# PCB_Minisumo_2018_Educatiu.net
KiCad netlist of a schematic drawn in EAGLE
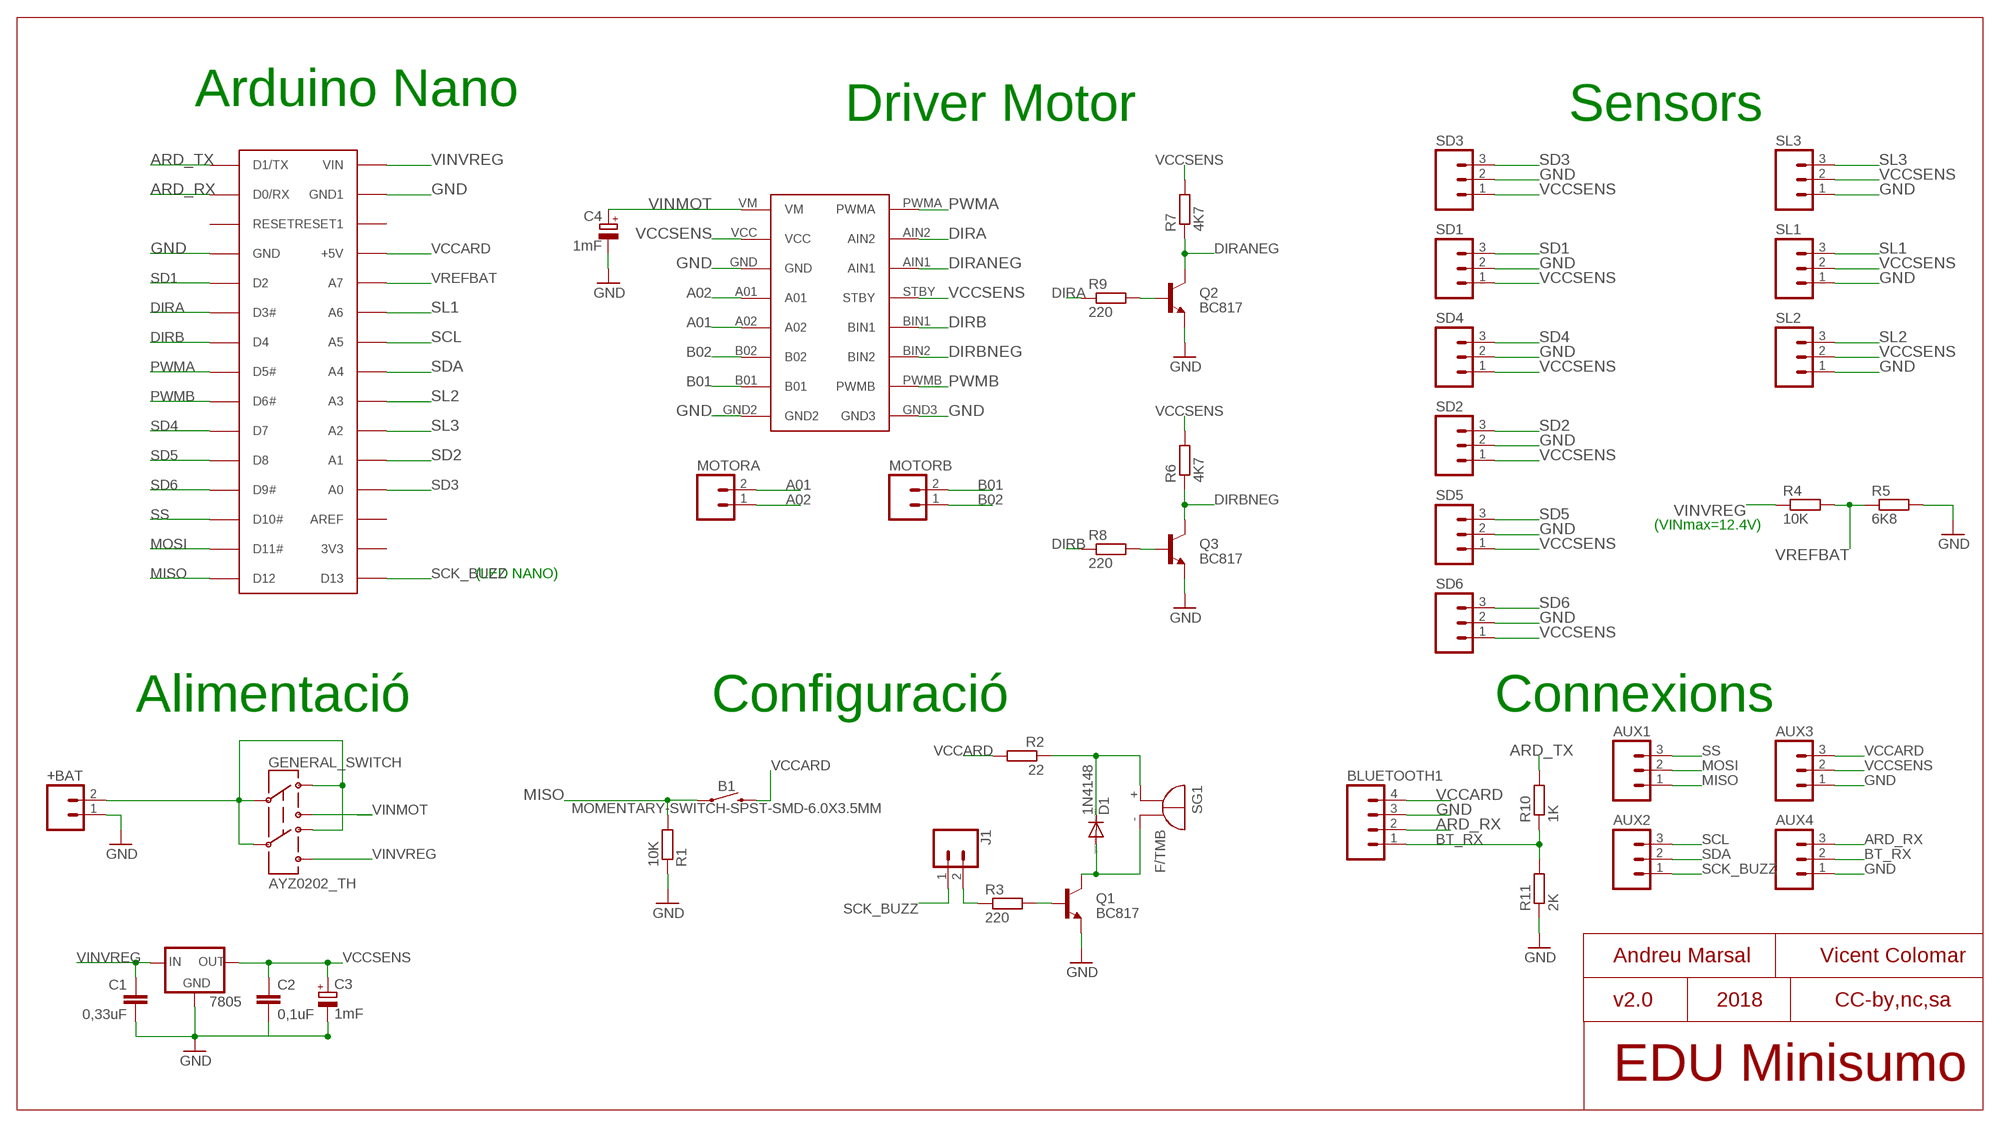
[diagram p0: schematic, sheet 1]
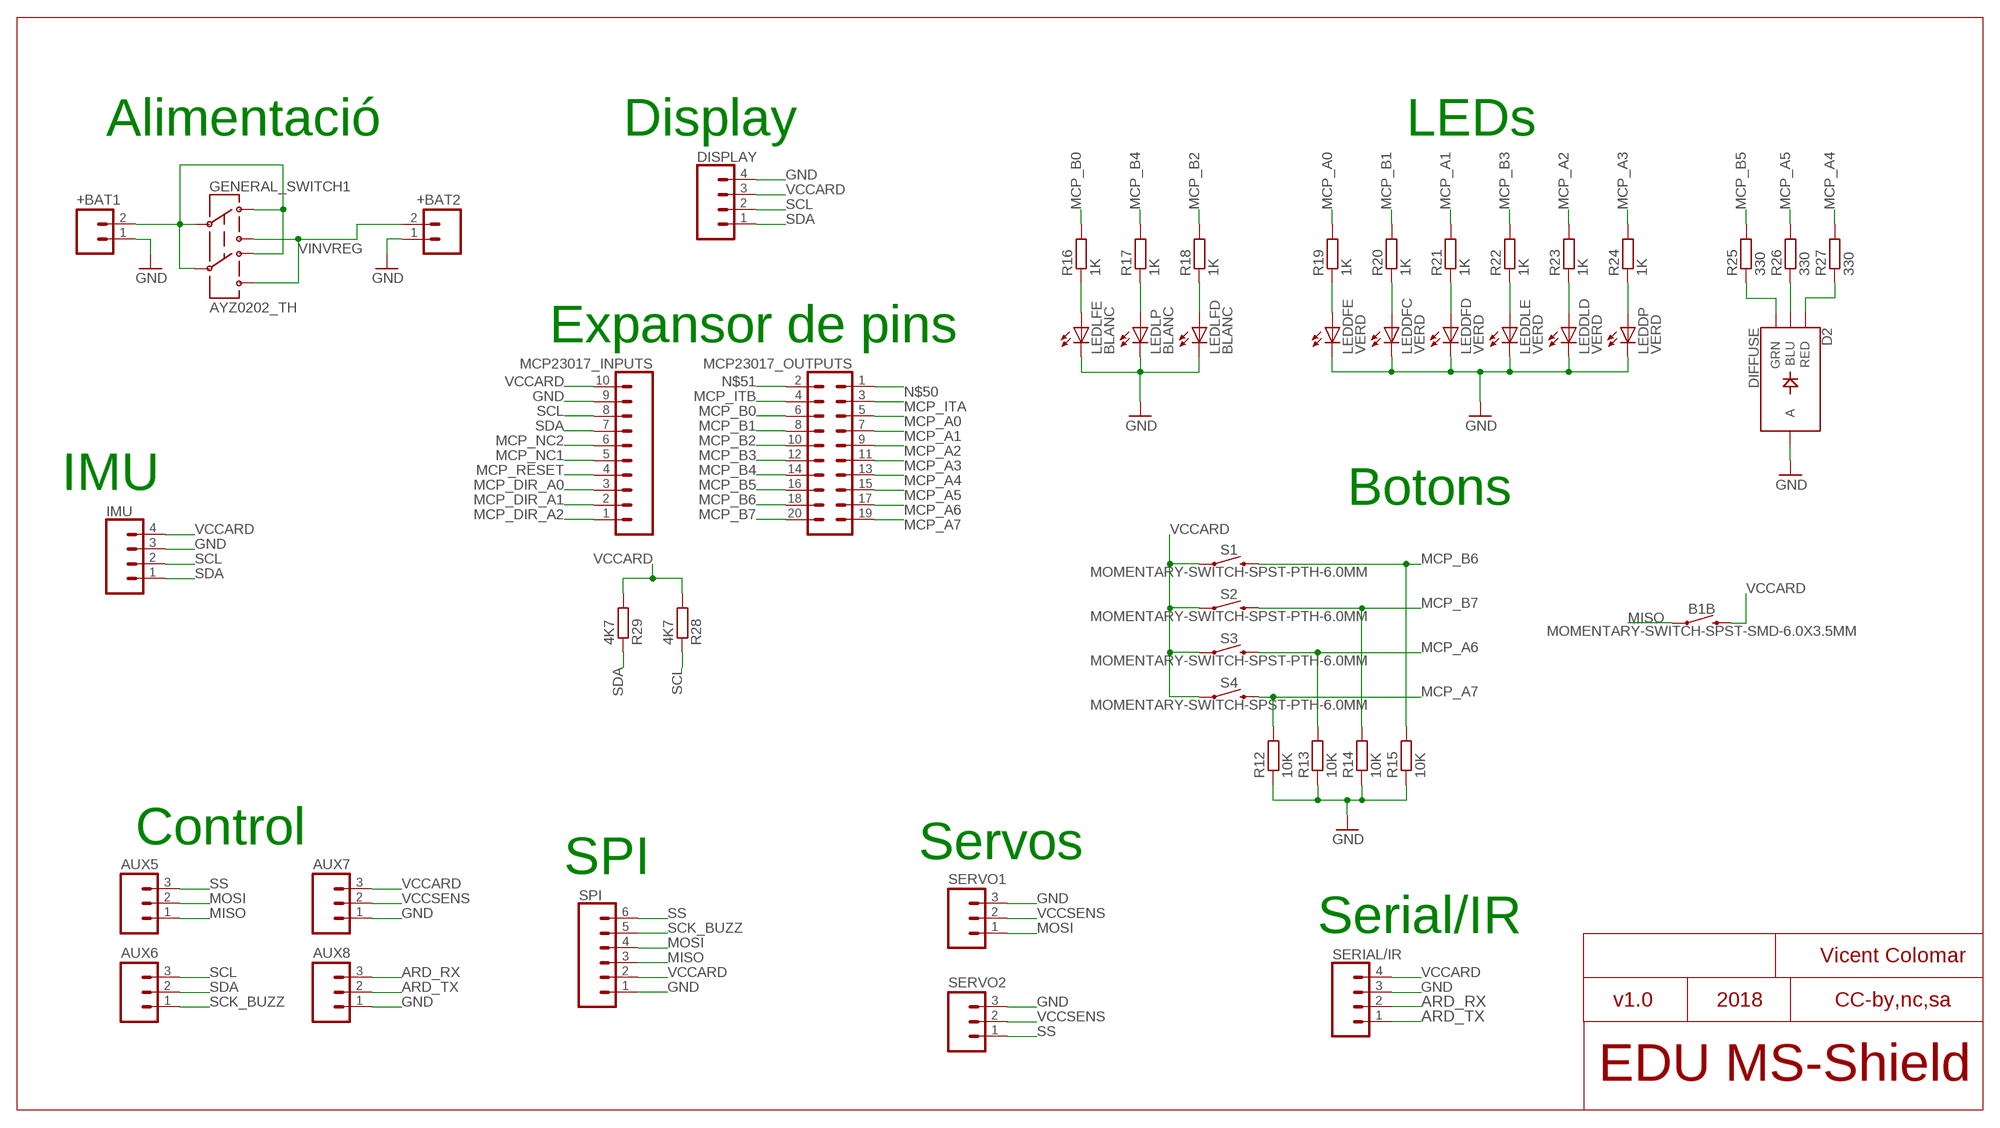
[diagram p1: schematic, sheet 2]

(export (version "E")
  (design (tool "Eeschema 10.0.6"))
  (components
    (comp (ref "+BAT")
      (value "M02LOCK_LONGPADS")
      (footprint "eagle-import:1X02_LOCK_LONGPADS")
      (libsource (lib "eagle-import") (part "M02LOCK_LONGPADS"))
    )
    (comp (ref "7805")
      (value "V_REG_78XXSINK")
      (footprint "eagle-import:TO220-IGO")
      (libsource (lib "eagle-import") (part "V_REG_78XXSINK"))
    )
    (comp (ref "AUX1")
      (value "M03PTH")
      (footprint "eagle-import:1X03")
      (libsource (lib "eagle-import") (part "M03PTH"))
    )
    (comp (ref "AUX2")
      (value "M03PTH")
      (footprint "eagle-import:1X03")
      (libsource (lib "eagle-import") (part "M03PTH"))
    )
    (comp (ref "AUX3")
      (value "M03PTH")
      (footprint "eagle-import:1X03")
      (libsource (lib "eagle-import") (part "M03PTH"))
    )
    (comp (ref "AUX4")
      (value "M03PTH")
      (footprint "eagle-import:1X03")
      (libsource (lib "eagle-import") (part "M03PTH"))
    )
    (comp (ref "B1")
      (value "MOMENTARY-SWITCH-SPST-SMD-6.0X3.5MM")
      (footprint "eagle-import:TACTILE_SWITCH_SMD_6.0X3.5MM")
      (libsource (lib "eagle-import") (part "MOMENTARY-SWITCH-SPST-SMD-6.0X3.5MM"))
    )
    (comp (ref "BLUETOOTH1")
      (value "M04PTH")
      (footprint "eagle-import:1X04")
      (libsource (lib "eagle-import") (part "M04PTH"))
    )
    (comp (ref "C1")
      (value "0,33uF")
      (footprint "eagle-import:C1206K")
      (libsource (lib "eagle-import") (part "C-EUC1206K"))
    )
    (comp (ref "C2")
      (value "0,1uF")
      (footprint "eagle-import:C1206K")
      (libsource (lib "eagle-import") (part "C-EUC1206K"))
    )
    (comp (ref "C3")
      (value "1mF")
      (footprint "eagle-import:E2,5-6")
      (libsource (lib "eagle-import") (part "CPOL-EUE2.5-6"))
    )
    (comp (ref "C4")
      (value "1mF")
      (footprint "eagle-import:E2,5-6")
      (libsource (lib "eagle-import") (part "CPOL-EUE2.5-6"))
    )
    (comp (ref "D1")
      (value "1N4148")
      (footprint "eagle-import:SOD106-R")
      (libsource (lib "eagle-import") (part "DIODE-SOD106-R"))
    )
    (comp (ref "GENERAL_SWITCH")
      (value "AYZ0202_TH")
      (footprint "eagle-import:AYZ0202_TH")
      (libsource (lib "eagle-import") (part "AYZ0202_TH"))
    )
    (comp (ref "J1")
      (value "CONN_02")
      (footprint "eagle-import:1X02")
      (libsource (lib "eagle-import") (part "CONN_02"))
    )
    (comp (ref "MOTORA")
      (value "M023.5MM")
      (footprint "eagle-import:SCREWTERMINAL-3.5MM-2")
      (libsource (lib "eagle-import") (part "M023.5MM"))
    )
    (comp (ref "MOTORB")
      (value "M023.5MM")
      (footprint "eagle-import:SCREWTERMINAL-3.5MM-2")
      (libsource (lib "eagle-import") (part "M023.5MM"))
    )
    (comp (ref "Q1")
      (value "BC817")
      (footprint "eagle-import:TO-92")
      (libsource (lib "eagle-import") (part "TRANSISTOR_NPNTO92"))
    )
    (comp (ref "Q2")
      (value "BC817")
      (footprint "eagle-import:TO-92")
      (libsource (lib "eagle-import") (part "TRANSISTOR_NPNTO92"))
    )
    (comp (ref "Q3")
      (value "BC817")
      (footprint "eagle-import:TO-92")
      (libsource (lib "eagle-import") (part "TRANSISTOR_NPNTO92"))
    )
    (comp (ref "R1")
      (value "10K")
      (footprint "eagle-import:R1206")
      (libsource (lib "eagle-import") (part "resistor_348_R-EU_R1206"))
    )
    (comp (ref "R2")
      (value "22")
      (footprint "eagle-import:R1206")
      (libsource (lib "eagle-import") (part "resistor_348_R-EU_R1206"))
    )
    (comp (ref "R3")
      (value "220")
      (footprint "eagle-import:M1206")
      (libsource (lib "eagle-import") (part "R-EU_M1206"))
    )
    (comp (ref "R4")
      (value "10K")
      (footprint "eagle-import:R1206")
      (libsource (lib "eagle-import") (part "resistor_348_R-EU_R1206"))
    )
    (comp (ref "R5")
      (value "6K8")
      (footprint "eagle-import:R1206")
      (libsource (lib "eagle-import") (part "resistor_348_R-EU_R1206"))
    )
    (comp (ref "R6")
      (value "4K7")
      (footprint "eagle-import:M1206")
      (libsource (lib "eagle-import") (part "R-EU_M1206"))
    )
    (comp (ref "R7")
      (value "4K7")
      (footprint "eagle-import:M1206")
      (libsource (lib "eagle-import") (part "R-EU_M1206"))
    )
    (comp (ref "R8")
      (value "220")
      (footprint "eagle-import:M1206")
      (libsource (lib "eagle-import") (part "R-EU_M1206"))
    )
    (comp (ref "R9")
      (value "220")
      (footprint "eagle-import:M1206")
      (libsource (lib "eagle-import") (part "R-EU_M1206"))
    )
    (comp (ref "R10")
      (value "1K")
      (footprint "eagle-import:R1206")
      (libsource (lib "eagle-import") (part "resistor_348_R-EU_R1206"))
    )
    (comp (ref "R11")
      (value "2K")
      (footprint "eagle-import:R1206")
      (libsource (lib "eagle-import") (part "resistor_348_R-EU_R1206"))
    )
    (comp (ref "SD1")
      (value "M03PTH")
      (footprint "eagle-import:1X03")
      (libsource (lib "eagle-import") (part "M03PTH"))
    )
    (comp (ref "SD2")
      (value "M03PTH")
      (footprint "eagle-import:1X03")
      (libsource (lib "eagle-import") (part "M03PTH"))
    )
    (comp (ref "SD3")
      (value "M03PTH")
      (footprint "eagle-import:1X03")
      (libsource (lib "eagle-import") (part "M03PTH"))
    )
    (comp (ref "SD4")
      (value "M03PTH")
      (footprint "eagle-import:1X03")
      (libsource (lib "eagle-import") (part "M03PTH"))
    )
    (comp (ref "SD5")
      (value "M03PTH")
      (footprint "eagle-import:1X03")
      (libsource (lib "eagle-import") (part "M03PTH"))
    )
    (comp (ref "SD6")
      (value "M03PTH")
      (footprint "eagle-import:1X03")
      (libsource (lib "eagle-import") (part "M03PTH"))
    )
    (comp (ref "SG1")
      (value "F/TMB")
      (footprint "eagle-import:F_TMB")
      (libsource (lib "eagle-import") (part "F/TMB"))
    )
    (comp (ref "SL1")
      (value "M03PTH")
      (footprint "eagle-import:1X03")
      (libsource (lib "eagle-import") (part "M03PTH"))
    )
    (comp (ref "SL2")
      (value "M03PTH")
      (footprint "eagle-import:1X03")
      (libsource (lib "eagle-import") (part "M03PTH"))
    )
    (comp (ref "SL3")
      (value "M03PTH")
      (footprint "eagle-import:1X03")
      (libsource (lib "eagle-import") (part "M03PTH"))
    )
    (comp (ref "U$1")
      (value "ARDUINONANONOHOLES")
      (footprint "eagle-import:PDIP-32NOHOLES")
      (libsource (lib "eagle-import") (part "ARDUINONANONOHOLES"))
    )
    (comp (ref "U$2")
      (value "TB6612FNG_SPARKFUN")
      (footprint "eagle-import:TB6612FNG_SPARKFUN")
      (libsource (lib "eagle-import") (part "TB6612FNG_SPARKFUN"))
    )
    (comp (ref "+BAT1")
      (value "M02LOCK_LONGPADS")
      (footprint "eagle-import:1X02_LOCK_LONGPADS")
      (libsource (lib "eagle-import") (part "M02LOCK_LONGPADS"))
    )
    (comp (ref "+BAT2")
      (value "M02LOCK_LONGPADS")
      (footprint "eagle-import:1X02_LOCK_LONGPADS")
      (libsource (lib "eagle-import") (part "M02LOCK_LONGPADS"))
    )
    (comp (ref "AUX5")
      (value "M03PTH")
      (footprint "eagle-import:1X03")
      (libsource (lib "eagle-import") (part "M03PTH"))
    )
    (comp (ref "AUX6")
      (value "M03PTH")
      (footprint "eagle-import:1X03")
      (libsource (lib "eagle-import") (part "M03PTH"))
    )
    (comp (ref "AUX7")
      (value "M03PTH")
      (footprint "eagle-import:1X03")
      (libsource (lib "eagle-import") (part "M03PTH"))
    )
    (comp (ref "AUX8")
      (value "M03PTH")
      (footprint "eagle-import:1X03")
      (libsource (lib "eagle-import") (part "M03PTH"))
    )
    (comp (ref "B1B")
      (value "MOMENTARY-SWITCH-SPST-SMD-6.0X3.5MM")
      (footprint "eagle-import:TACTILE_SWITCH_SMD_6.0X3.5MM")
      (libsource (lib "eagle-import") (part "MOMENTARY-SWITCH-SPST-SMD-6.0X3.5MM"))
    )
    (comp (ref "D2")
      (value "DIFFUSE")
      (footprint "eagle-import:LED-RGB-THRU")
      (libsource (lib "eagle-import") (part "LED-RGB-CADIFFUSE"))
    )
    (comp (ref "DISPLAY")
      (value "CONN_04")
      (footprint "eagle-import:1X04")
      (libsource (lib "eagle-import") (part "CONN_04"))
    )
    (comp (ref "GENERAL_SWITCH1")
      (value "AYZ0202_TH")
      (footprint "eagle-import:AYZ0202_TH")
      (libsource (lib "eagle-import") (part "AYZ0202_TH"))
    )
    (comp (ref "IMU")
      (value "CONN_04")
      (footprint "eagle-import:1X04")
      (libsource (lib "eagle-import") (part "CONN_04"))
    )
    (comp (ref "LEDDFC")
      (value "VERD")
      (footprint "eagle-import:1206")
      (libsource (lib "eagle-import") (part "LEDSMT1206"))
    )
    (comp (ref "LEDDFD")
      (value "VERD")
      (footprint "eagle-import:1206")
      (libsource (lib "eagle-import") (part "LEDSMT1206"))
    )
    (comp (ref "LEDDFE")
      (value "VERD")
      (footprint "eagle-import:1206")
      (libsource (lib "eagle-import") (part "LEDSMT1206"))
    )
    (comp (ref "LEDDLD")
      (value "VERD")
      (footprint "eagle-import:1206")
      (libsource (lib "eagle-import") (part "LEDSMT1206"))
    )
    (comp (ref "LEDDLE")
      (value "VERD")
      (footprint "eagle-import:1206")
      (libsource (lib "eagle-import") (part "LEDSMT1206"))
    )
    (comp (ref "LEDDP")
      (value "VERD")
      (footprint "eagle-import:1206")
      (libsource (lib "eagle-import") (part "LEDSMT1206"))
    )
    (comp (ref "LEDLFD")
      (value "BLANC")
      (footprint "eagle-import:1206")
      (libsource (lib "eagle-import") (part "LEDSMT1206"))
    )
    (comp (ref "LEDLFE")
      (value "BLANC")
      (footprint "eagle-import:1206")
      (libsource (lib "eagle-import") (part "LEDSMT1206"))
    )
    (comp (ref "LEDLP")
      (value "BLANC")
      (footprint "eagle-import:1206")
      (libsource (lib "eagle-import") (part "LEDSMT1206"))
    )
    (comp (ref "MCP23017_INPUTS")
      (value "CONN_10\"")
      (footprint "eagle-import:1X10")
      (libsource (lib "eagle-import") (part "CONN_10{dblquote}"))
    )
    (comp (ref "MCP23017_OUTPUTS")
      (value "CONN_10X2")
      (footprint "eagle-import:2X10")
      (libsource (lib "eagle-import") (part "CONN_10X2"))
    )
    (comp (ref "R12")
      (value "10K")
      (footprint "eagle-import:M1206")
      (libsource (lib "eagle-import") (part "R-EU_M1206"))
    )
    (comp (ref "R13")
      (value "10K")
      (footprint "eagle-import:M1206")
      (libsource (lib "eagle-import") (part "R-EU_M1206"))
    )
    (comp (ref "R14")
      (value "10K")
      (footprint "eagle-import:M1206")
      (libsource (lib "eagle-import") (part "R-EU_M1206"))
    )
    (comp (ref "R15")
      (value "10K")
      (footprint "eagle-import:M1206")
      (libsource (lib "eagle-import") (part "R-EU_M1206"))
    )
    (comp (ref "R16")
      (value "1K")
      (footprint "eagle-import:M1206")
      (libsource (lib "eagle-import") (part "R-EU_M1206"))
    )
    (comp (ref "R17")
      (value "1K")
      (footprint "eagle-import:M1206")
      (libsource (lib "eagle-import") (part "R-EU_M1206"))
    )
    (comp (ref "R18")
      (value "1K")
      (footprint "eagle-import:M1206")
      (libsource (lib "eagle-import") (part "R-EU_M1206"))
    )
    (comp (ref "R19")
      (value "1K")
      (footprint "eagle-import:M1206")
      (libsource (lib "eagle-import") (part "R-EU_M1206"))
    )
    (comp (ref "R20")
      (value "1K")
      (footprint "eagle-import:M1206")
      (libsource (lib "eagle-import") (part "R-EU_M1206"))
    )
    (comp (ref "R21")
      (value "1K")
      (footprint "eagle-import:M1206")
      (libsource (lib "eagle-import") (part "R-EU_M1206"))
    )
    (comp (ref "R22")
      (value "1K")
      (footprint "eagle-import:M1206")
      (libsource (lib "eagle-import") (part "R-EU_M1206"))
    )
    (comp (ref "R23")
      (value "1K")
      (footprint "eagle-import:M1206")
      (libsource (lib "eagle-import") (part "R-EU_M1206"))
    )
    (comp (ref "R24")
      (value "1K")
      (footprint "eagle-import:M1206")
      (libsource (lib "eagle-import") (part "R-EU_M1206"))
    )
    (comp (ref "R25")
      (value "330")
      (footprint "eagle-import:M1206")
      (libsource (lib "eagle-import") (part "R-EU_M1206"))
    )
    (comp (ref "R26")
      (value "330")
      (footprint "eagle-import:M1206")
      (libsource (lib "eagle-import") (part "R-EU_M1206"))
    )
    (comp (ref "R27")
      (value "330")
      (footprint "eagle-import:M1206")
      (libsource (lib "eagle-import") (part "R-EU_M1206"))
    )
    (comp (ref "R28")
      (value "4K7")
      (footprint "eagle-import:M1206")
      (libsource (lib "eagle-import") (part "R-EU_M1206"))
    )
    (comp (ref "R29")
      (value "4K7")
      (footprint "eagle-import:M1206")
      (libsource (lib "eagle-import") (part "R-EU_M1206"))
    )
    (comp (ref "S1")
      (value "MOMENTARY-SWITCH-SPST-PTH-6.0MM")
      (footprint "eagle-import:TACTILE_SWITCH_PTH_6.0MM")
      (libsource (lib "eagle-import") (part "MOMENTARY-SWITCH-SPST-PTH-6.0MM"))
    )
    (comp (ref "S2")
      (value "MOMENTARY-SWITCH-SPST-PTH-6.0MM")
      (footprint "eagle-import:TACTILE_SWITCH_PTH_6.0MM")
      (libsource (lib "eagle-import") (part "MOMENTARY-SWITCH-SPST-PTH-6.0MM"))
    )
    (comp (ref "S3")
      (value "MOMENTARY-SWITCH-SPST-PTH-6.0MM")
      (footprint "eagle-import:TACTILE_SWITCH_PTH_6.0MM")
      (libsource (lib "eagle-import") (part "MOMENTARY-SWITCH-SPST-PTH-6.0MM"))
    )
    (comp (ref "S4")
      (value "MOMENTARY-SWITCH-SPST-PTH-6.0MM")
      (footprint "eagle-import:TACTILE_SWITCH_PTH_6.0MM")
      (libsource (lib "eagle-import") (part "MOMENTARY-SWITCH-SPST-PTH-6.0MM"))
    )
    (comp (ref "SERIAL/IR")
      (value "CONN_04")
      (footprint "eagle-import:1X04")
      (libsource (lib "eagle-import") (part "CONN_04"))
    )
    (comp (ref "SERVO1")
      (value "M03PTH")
      (footprint "eagle-import:1X03")
      (libsource (lib "eagle-import") (part "M03PTH"))
    )
    (comp (ref "SERVO2")
      (value "M03PTH")
      (footprint "eagle-import:1X03")
      (libsource (lib "eagle-import") (part "M03PTH"))
    )
    (comp (ref "SPI")
      (value "CONN_06SILK_FEMALE_PTH")
      (footprint "eagle-import:1X06")
      (libsource (lib "eagle-import") (part "CONN_06SILK_FEMALE_PTH"))
    )
  )
  (nets
    (net (code "1") (name "A01") (class "Default")
      (node (ref "MOTORA") (pin "2") (pinfunction "2_2") (pintype "passive"))
      (node (ref "U$2") (pin "A02") (pinfunction "A02_A02") (pintype "bidirectional"))
    )
    (net (code "2") (name "A02") (class "Default")
      (node (ref "MOTORA") (pin "1") (pinfunction "1_1") (pintype "passive"))
      (node (ref "U$2") (pin "A01") (pinfunction "A01_A01") (pintype "bidirectional"))
    )
    (net (code "3") (name "ARD_RX") (class "Default")
      (node (ref "AUX4") (pin "3") (pinfunction "3_3") (pintype "passive"))
      (node (ref "AUX8") (pin "3") (pinfunction "3_3") (pintype "passive"))
      (node (ref "BLUETOOTH1") (pin "2") (pinfunction "2_2") (pintype "passive"))
      (node (ref "SERIAL/IR") (pin "2") (pinfunction "2_2") (pintype "passive"))
      (node (ref "U$1") (pin "D0/RX") (pinfunction "D0/RX_D0/RX") (pintype "bidirectional"))
    )
    (net (code "4") (name "ARD_TX") (class "Default")
      (node (ref "AUX8") (pin "2") (pinfunction "2_2") (pintype "passive"))
      (node (ref "R10") (pin "2") (pinfunction "2_2") (pintype "passive"))
      (node (ref "SERIAL/IR") (pin "1") (pinfunction "1_1") (pintype "passive"))
      (node (ref "U$1") (pin "D1/TX") (pinfunction "D1/TX_D1/TX") (pintype "bidirectional"))
    )
    (net (code "5") (name "B01") (class "Default")
      (node (ref "MOTORB") (pin "2") (pinfunction "2_2") (pintype "passive"))
      (node (ref "U$2") (pin "B01") (pinfunction "B01_B01") (pintype "bidirectional"))
    )
    (net (code "6") (name "B02") (class "Default")
      (node (ref "MOTORB") (pin "1") (pinfunction "1_1") (pintype "passive"))
      (node (ref "U$2") (pin "B02") (pinfunction "B02_B02") (pintype "bidirectional"))
    )
    (net (code "7") (name "BT_RX") (class "Default")
      (node (ref "AUX4") (pin "2") (pinfunction "2_2") (pintype "passive"))
      (node (ref "BLUETOOTH1") (pin "1") (pinfunction "1_1") (pintype "passive"))
      (node (ref "R10") (pin "1") (pinfunction "1_1") (pintype "passive"))
      (node (ref "R11") (pin "2") (pinfunction "2_2") (pintype "passive"))
    )
    (net (code "8") (name "DIRA") (class "Default")
      (node (ref "R9") (pin "1") (pinfunction "1_1") (pintype "passive"))
      (node (ref "U$1") (pin "D3") (pinfunction "D3#_D3") (pintype "bidirectional"))
      (node (ref "U$2") (pin "AIN2") (pinfunction "AIN2_AIN2") (pintype "bidirectional"))
    )
    (net (code "9") (name "DIRANEG") (class "Default")
      (node (ref "Q2") (pin "3") (pinfunction "C_3") (pintype "passive"))
      (node (ref "R7") (pin "1") (pinfunction "1_1") (pintype "passive"))
      (node (ref "U$2") (pin "AIN1") (pinfunction "AIN1_AIN1") (pintype "bidirectional"))
    )
    (net (code "10") (name "DIRB") (class "Default")
      (node (ref "R8") (pin "1") (pinfunction "1_1") (pintype "passive"))
      (node (ref "U$1") (pin "D4") (pinfunction "D4_D4") (pintype "bidirectional"))
      (node (ref "U$2") (pin "BIN1") (pinfunction "BIN1_BIN1") (pintype "bidirectional"))
    )
    (net (code "11") (name "DIRBNEG") (class "Default")
      (node (ref "Q3") (pin "3") (pinfunction "C_3") (pintype "passive"))
      (node (ref "R6") (pin "1") (pinfunction "1_1") (pintype "passive"))
      (node (ref "U$2") (pin "BIN2") (pinfunction "BIN2_BIN2") (pintype "bidirectional"))
    )
    (net (code "12") (name "GND") (class "Default")
      (node (ref "+BAT") (pin "1") (pinfunction "1_1") (pintype "passive"))
      (node (ref "+BAT1") (pin "1") (pinfunction "1_1") (pintype "passive"))
      (node (ref "+BAT2") (pin "1") (pinfunction "1_1") (pintype "passive"))
      (node (ref "7805") (pin "GND") (pinfunction "GND_GND") (pintype "input"))
      (node (ref "AUX3") (pin "1") (pinfunction "1_1") (pintype "passive"))
      (node (ref "AUX4") (pin "1") (pinfunction "1_1") (pintype "passive"))
      (node (ref "AUX7") (pin "1") (pinfunction "1_1") (pintype "passive"))
      (node (ref "AUX8") (pin "1") (pinfunction "1_1") (pintype "passive"))
      (node (ref "BLUETOOTH1") (pin "3") (pinfunction "3_3") (pintype "passive"))
      (node (ref "C1") (pin "2") (pinfunction "2_2") (pintype "passive"))
      (node (ref "C2") (pin "2") (pinfunction "2_2") (pintype "passive"))
      (node (ref "C3") (pin "-") (pinfunction "-_-") (pintype "passive"))
      (node (ref "C4") (pin "-") (pinfunction "-_-") (pintype "passive"))
      (node (ref "D2") (pin "2") (pinfunction "A_2") (pintype "bidirectional"))
      (node (ref "DISPLAY") (pin "4") (pinfunction "4_4") (pintype "passive"))
      (node (ref "IMU") (pin "3") (pinfunction "3_3") (pintype "passive"))
      (node (ref "LEDDFC") (pin "C") (pinfunction "C_C") (pintype "passive"))
      (node (ref "LEDDFD") (pin "C") (pinfunction "C_C") (pintype "passive"))
      (node (ref "LEDDFE") (pin "C") (pinfunction "C_C") (pintype "passive"))
      (node (ref "LEDDLD") (pin "C") (pinfunction "C_C") (pintype "passive"))
      (node (ref "LEDDLE") (pin "C") (pinfunction "C_C") (pintype "passive"))
      (node (ref "LEDDP") (pin "C") (pinfunction "C_C") (pintype "passive"))
      (node (ref "LEDLFD") (pin "C") (pinfunction "C_C") (pintype "passive"))
      (node (ref "LEDLFE") (pin "C") (pinfunction "C_C") (pintype "passive"))
      (node (ref "LEDLP") (pin "C") (pinfunction "C_C") (pintype "passive"))
      (node (ref "MCP23017_INPUTS") (pin "9") (pinfunction "9_9") (pintype "passive"))
      (node (ref "Q1") (pin "1") (pinfunction "E_1") (pintype "passive"))
      (node (ref "Q2") (pin "1") (pinfunction "E_1") (pintype "passive"))
      (node (ref "Q3") (pin "1") (pinfunction "E_1") (pintype "passive"))
      (node (ref "R1") (pin "1") (pinfunction "1_1") (pintype "passive"))
      (node (ref "R11") (pin "1") (pinfunction "1_1") (pintype "passive"))
      (node (ref "R12") (pin "1") (pinfunction "1_1") (pintype "passive"))
      (node (ref "R13") (pin "1") (pinfunction "1_1") (pintype "passive"))
      (node (ref "R14") (pin "1") (pinfunction "1_1") (pintype "passive"))
      (node (ref "R15") (pin "1") (pinfunction "1_1") (pintype "passive"))
      (node (ref "R5") (pin "2") (pinfunction "2_2") (pintype "passive"))
      (node (ref "SD1") (pin "2") (pinfunction "2_2") (pintype "passive"))
      (node (ref "SD2") (pin "2") (pinfunction "2_2") (pintype "passive"))
      (node (ref "SD3") (pin "2") (pinfunction "2_2") (pintype "passive"))
      (node (ref "SD4") (pin "2") (pinfunction "2_2") (pintype "passive"))
      (node (ref "SD5") (pin "2") (pinfunction "2_2") (pintype "passive"))
      (node (ref "SD6") (pin "2") (pinfunction "2_2") (pintype "passive"))
      (node (ref "SERIAL/IR") (pin "3") (pinfunction "3_3") (pintype "passive"))
      (node (ref "SERVO1") (pin "3") (pinfunction "3_3") (pintype "passive"))
      (node (ref "SERVO2") (pin "3") (pinfunction "3_3") (pintype "passive"))
      (node (ref "SL1") (pin "1") (pinfunction "1_1") (pintype "passive"))
      (node (ref "SL2") (pin "1") (pinfunction "1_1") (pintype "passive"))
      (node (ref "SL3") (pin "1") (pinfunction "1_1") (pintype "passive"))
      (node (ref "SPI") (pin "1") (pinfunction "1_1") (pintype "passive"))
      (node (ref "U$1") (pin "GND") (pinfunction "GND_GND") (pintype "bidirectional"))
      (node (ref "U$1") (pin "GND1") (pinfunction "GND1_GND1") (pintype "bidirectional"))
      (node (ref "U$2") (pin "GND") (pinfunction "GND_GND") (pintype "bidirectional"))
      (node (ref "U$2") (pin "GND2") (pinfunction "GND2_GND2") (pintype "bidirectional"))
      (node (ref "U$2") (pin "GND3") (pinfunction "GND3_GND3") (pintype "bidirectional"))
    )
    (net (code "13") (name "MCP_A0") (class "Default")
      (node (ref "MCP23017_OUTPUTS") (pin "5") (pinfunction "5_5") (pintype "passive"))
      (node (ref "R19") (pin "2") (pinfunction "2_2") (pintype "passive"))
    )
    (net (code "14") (name "MCP_A1") (class "Default")
      (node (ref "MCP23017_OUTPUTS") (pin "7") (pinfunction "7_7") (pintype "passive"))
      (node (ref "R21") (pin "2") (pinfunction "2_2") (pintype "passive"))
    )
    (net (code "15") (name "MCP_A2") (class "Default")
      (node (ref "MCP23017_OUTPUTS") (pin "9") (pinfunction "9_9") (pintype "passive"))
      (node (ref "R23") (pin "2") (pinfunction "2_2") (pintype "passive"))
    )
    (net (code "16") (name "MCP_A3") (class "Default")
      (node (ref "MCP23017_OUTPUTS") (pin "11") (pinfunction "11_11") (pintype "passive"))
      (node (ref "R24") (pin "2") (pinfunction "2_2") (pintype "passive"))
    )
    (net (code "17") (name "MCP_A4") (class "Default")
      (node (ref "MCP23017_OUTPUTS") (pin "13") (pinfunction "13_13") (pintype "passive"))
      (node (ref "R27") (pin "2") (pinfunction "2_2") (pintype "passive"))
    )
    (net (code "18") (name "MCP_A5") (class "Default")
      (node (ref "MCP23017_OUTPUTS") (pin "15") (pinfunction "15_15") (pintype "passive"))
      (node (ref "R26") (pin "2") (pinfunction "2_2") (pintype "passive"))
    )
    (net (code "19") (name "MCP_A6") (class "Default")
      (node (ref "MCP23017_OUTPUTS") (pin "17") (pinfunction "17_17") (pintype "passive"))
      (node (ref "R13") (pin "2") (pinfunction "2_2") (pintype "passive"))
      (node (ref "S3") (pin "3") (pinfunction "2_3") (pintype "passive"))
    )
    (net (code "20") (name "MCP_A7") (class "Default")
      (node (ref "MCP23017_OUTPUTS") (pin "19") (pinfunction "19_19") (pintype "passive"))
      (node (ref "R12") (pin "2") (pinfunction "2_2") (pintype "passive"))
      (node (ref "S4") (pin "3") (pinfunction "2_3") (pintype "passive"))
    )
    (net (code "21") (name "MCP_B0") (class "Default")
      (node (ref "MCP23017_OUTPUTS") (pin "6") (pinfunction "6_6") (pintype "passive"))
      (node (ref "R16") (pin "2") (pinfunction "2_2") (pintype "passive"))
    )
    (net (code "22") (name "MCP_B1") (class "Default")
      (node (ref "MCP23017_OUTPUTS") (pin "8") (pinfunction "8_8") (pintype "passive"))
      (node (ref "R20") (pin "2") (pinfunction "2_2") (pintype "passive"))
    )
    (net (code "23") (name "MCP_B2") (class "Default")
      (node (ref "MCP23017_OUTPUTS") (pin "10") (pinfunction "10_10") (pintype "passive"))
      (node (ref "R18") (pin "2") (pinfunction "2_2") (pintype "passive"))
    )
    (net (code "24") (name "MCP_B3") (class "Default")
      (node (ref "MCP23017_OUTPUTS") (pin "12") (pinfunction "12_12") (pintype "passive"))
      (node (ref "R22") (pin "2") (pinfunction "2_2") (pintype "passive"))
    )
    (net (code "25") (name "MCP_B4") (class "Default")
      (node (ref "MCP23017_OUTPUTS") (pin "14") (pinfunction "14_14") (pintype "passive"))
      (node (ref "R17") (pin "2") (pinfunction "2_2") (pintype "passive"))
    )
    (net (code "26") (name "MCP_B5") (class "Default")
      (node (ref "MCP23017_OUTPUTS") (pin "16") (pinfunction "16_16") (pintype "passive"))
      (node (ref "R25") (pin "2") (pinfunction "2_2") (pintype "passive"))
    )
    (net (code "27") (name "MCP_B6") (class "Default")
      (node (ref "MCP23017_OUTPUTS") (pin "18") (pinfunction "18_18") (pintype "passive"))
      (node (ref "R15") (pin "2") (pinfunction "2_2") (pintype "passive"))
      (node (ref "S1") (pin "3") (pinfunction "2_3") (pintype "passive"))
    )
    (net (code "28") (name "MCP_B7") (class "Default")
      (node (ref "MCP23017_OUTPUTS") (pin "20") (pinfunction "20_20") (pintype "passive"))
      (node (ref "R14") (pin "2") (pinfunction "2_2") (pintype "passive"))
      (node (ref "S2") (pin "3") (pinfunction "2_3") (pintype "passive"))
    )
    (net (code "29") (name "MCP_DIR_A0") (class "Default")
      (node (ref "MCP23017_INPUTS") (pin "3") (pinfunction "3_3") (pintype "passive"))
    )
    (net (code "30") (name "MCP_DIR_A1") (class "Default")
      (node (ref "MCP23017_INPUTS") (pin "2") (pinfunction "2_2") (pintype "passive"))
    )
    (net (code "31") (name "MCP_DIR_A2") (class "Default")
      (node (ref "MCP23017_INPUTS") (pin "1") (pinfunction "1_1") (pintype "passive"))
    )
    (net (code "32") (name "MCP_ITA") (class "Default")
      (node (ref "MCP23017_OUTPUTS") (pin "3") (pinfunction "3_3") (pintype "passive"))
    )
    (net (code "33") (name "MCP_ITB") (class "Default")
      (node (ref "MCP23017_OUTPUTS") (pin "4") (pinfunction "4_4") (pintype "passive"))
    )
    (net (code "34") (name "MCP_NC1") (class "Default")
      (node (ref "MCP23017_INPUTS") (pin "5") (pinfunction "5_5") (pintype "passive"))
    )
    (net (code "35") (name "MCP_NC2") (class "Default")
      (node (ref "MCP23017_INPUTS") (pin "6") (pinfunction "6_6") (pintype "passive"))
    )
    (net (code "36") (name "MCP_RESET") (class "Default")
      (node (ref "MCP23017_INPUTS") (pin "4") (pinfunction "4_4") (pintype "passive"))
    )
    (net (code "37") (name "MISO") (class "Default")
      (node (ref "AUX1") (pin "1") (pinfunction "1_1") (pintype "passive"))
      (node (ref "AUX5") (pin "1") (pinfunction "1_1") (pintype "passive"))
      (node (ref "B1") (pin "1") (pinfunction "1_1") (pintype "passive"))
      (node (ref "B1B") (pin "1") (pinfunction "1_1") (pintype "passive"))
      (node (ref "R1") (pin "2") (pinfunction "2_2") (pintype "passive"))
      (node (ref "SPI") (pin "3") (pinfunction "3_3") (pintype "passive"))
      (node (ref "U$1") (pin "D12") (pinfunction "D12_D12") (pintype "bidirectional"))
    )
    (net (code "38") (name "MOSI") (class "Default")
      (node (ref "AUX1") (pin "2") (pinfunction "2_2") (pintype "passive"))
      (node (ref "AUX5") (pin "2") (pinfunction "2_2") (pintype "passive"))
      (node (ref "SERVO1") (pin "1") (pinfunction "1_1") (pintype "passive"))
      (node (ref "SPI") (pin "4") (pinfunction "4_4") (pintype "passive"))
      (node (ref "U$1") (pin "D11") (pinfunction "D11#_D11") (pintype "bidirectional"))
    )
    (net (code "39") (name "N$50") (class "Default")
      (node (ref "MCP23017_OUTPUTS") (pin "1") (pinfunction "1_1") (pintype "passive"))
    )
    (net (code "40") (name "N$51") (class "Default")
      (node (ref "MCP23017_OUTPUTS") (pin "2") (pinfunction "2_2") (pintype "passive"))
    )
    (net (code "41") (name "Net-(+BAT-Pad2)") (class "Default")
      (node (ref "+BAT") (pin "2") (pinfunction "2_2") (pintype "passive"))
      (node (ref "GENERAL_SWITCH") (pin "C1") (pinfunction "C1_C1") (pintype "bidirectional"))
      (node (ref "GENERAL_SWITCH") (pin "C2") (pinfunction "C2_C2") (pintype "bidirectional"))
      (node (ref "GENERAL_SWITCH") (pin "D1") (pinfunction "D1_D1") (pintype "bidirectional"))
      (node (ref "GENERAL_SWITCH") (pin "D2") (pinfunction "D2_D2") (pintype "bidirectional"))
    )
    (net (code "42") (name "Net-(+BAT1-Pad2)") (class "Default")
      (node (ref "+BAT1") (pin "2") (pinfunction "2_2") (pintype "passive"))
      (node (ref "GENERAL_SWITCH1") (pin "C1") (pinfunction "C1_C1") (pintype "bidirectional"))
      (node (ref "GENERAL_SWITCH1") (pin "C2") (pinfunction "C2_C2") (pintype "bidirectional"))
      (node (ref "GENERAL_SWITCH1") (pin "D1") (pinfunction "D1_D1") (pintype "bidirectional"))
      (node (ref "GENERAL_SWITCH1") (pin "D2") (pinfunction "D2_D2") (pintype "bidirectional"))
    )
    (net (code "43") (name "Net-(D1-PadC)") (class "Default")
      (node (ref "D1") (pin "C") (pinfunction "C_C") (pintype "passive"))
      (node (ref "R2") (pin "1") (pinfunction "1_1") (pintype "passive"))
      (node (ref "SG1") (pin "+") (pinfunction "+_+") (pintype "passive"))
    )
    (net (code "44") (name "Net-(D2-BLU)") (class "Default")
      (node (ref "D2") (pin "4") (pinfunction "BLU_4") (pintype "bidirectional"))
      (node (ref "R26") (pin "1") (pinfunction "1_1") (pintype "passive"))
    )
    (net (code "45") (name "Net-(D2-GRN)") (class "Default")
      (node (ref "D2") (pin "3") (pinfunction "GRN_3") (pintype "bidirectional"))
      (node (ref "R25") (pin "1") (pinfunction "1_1") (pintype "passive"))
    )
    (net (code "46") (name "Net-(D2-RED)") (class "Default")
      (node (ref "D2") (pin "1") (pinfunction "RED_1") (pintype "bidirectional"))
      (node (ref "R27") (pin "1") (pinfunction "1_1") (pintype "passive"))
    )
    (net (code "47") (name "Net-(J1-Pad2)") (class "Default")
      (node (ref "J1") (pin "2") (pinfunction "2_2") (pintype "passive"))
      (node (ref "R3") (pin "1") (pinfunction "1_1") (pintype "passive"))
    )
    (net (code "48") (name "Net-(LEDDFC-PadA)") (class "Default")
      (node (ref "LEDDFC") (pin "A") (pinfunction "A_A") (pintype "passive"))
      (node (ref "R20") (pin "1") (pinfunction "1_1") (pintype "passive"))
    )
    (net (code "49") (name "Net-(LEDDFD-PadA)") (class "Default")
      (node (ref "LEDDFD") (pin "A") (pinfunction "A_A") (pintype "passive"))
      (node (ref "R21") (pin "1") (pinfunction "1_1") (pintype "passive"))
    )
    (net (code "50") (name "Net-(LEDDFE-PadA)") (class "Default")
      (node (ref "LEDDFE") (pin "A") (pinfunction "A_A") (pintype "passive"))
      (node (ref "R19") (pin "1") (pinfunction "1_1") (pintype "passive"))
    )
    (net (code "51") (name "Net-(LEDDLD-PadA)") (class "Default")
      (node (ref "LEDDLD") (pin "A") (pinfunction "A_A") (pintype "passive"))
      (node (ref "R23") (pin "1") (pinfunction "1_1") (pintype "passive"))
    )
    (net (code "52") (name "Net-(LEDDLE-PadA)") (class "Default")
      (node (ref "LEDDLE") (pin "A") (pinfunction "A_A") (pintype "passive"))
      (node (ref "R22") (pin "1") (pinfunction "1_1") (pintype "passive"))
    )
    (net (code "53") (name "Net-(LEDDP-PadA)") (class "Default")
      (node (ref "LEDDP") (pin "A") (pinfunction "A_A") (pintype "passive"))
      (node (ref "R24") (pin "1") (pinfunction "1_1") (pintype "passive"))
    )
    (net (code "54") (name "Net-(LEDLFD-PadA)") (class "Default")
      (node (ref "LEDLFD") (pin "A") (pinfunction "A_A") (pintype "passive"))
      (node (ref "R18") (pin "1") (pinfunction "1_1") (pintype "passive"))
    )
    (net (code "55") (name "Net-(LEDLFE-PadA)") (class "Default")
      (node (ref "LEDLFE") (pin "A") (pinfunction "A_A") (pintype "passive"))
      (node (ref "R16") (pin "1") (pinfunction "1_1") (pintype "passive"))
    )
    (net (code "56") (name "Net-(LEDLP-PadA)") (class "Default")
      (node (ref "LEDLP") (pin "A") (pinfunction "A_A") (pintype "passive"))
      (node (ref "R17") (pin "1") (pinfunction "1_1") (pintype "passive"))
    )
    (net (code "57") (name "Net-(Q1-B)") (class "Default")
      (node (ref "Q1") (pin "2") (pinfunction "B_2") (pintype "passive"))
      (node (ref "R3") (pin "2") (pinfunction "2_2") (pintype "passive"))
    )
    (net (code "58") (name "Net-(Q1-C)") (class "Default")
      (node (ref "D1") (pin "A") (pinfunction "A_A") (pintype "passive"))
      (node (ref "Q1") (pin "3") (pinfunction "C_3") (pintype "passive"))
      (node (ref "SG1") (pin "-") (pinfunction "-_-") (pintype "passive"))
    )
    (net (code "59") (name "Net-(Q2-B)") (class "Default")
      (node (ref "Q2") (pin "2") (pinfunction "B_2") (pintype "passive"))
      (node (ref "R9") (pin "2") (pinfunction "2_2") (pintype "passive"))
    )
    (net (code "60") (name "Net-(Q3-B)") (class "Default")
      (node (ref "Q3") (pin "2") (pinfunction "B_2") (pintype "passive"))
      (node (ref "R8") (pin "2") (pinfunction "2_2") (pintype "passive"))
    )
    (net (code "61") (name "PWMA") (class "Default")
      (node (ref "U$1") (pin "D5") (pinfunction "D5#_D5") (pintype "bidirectional"))
      (node (ref "U$2") (pin "PWMA") (pinfunction "PWMA_PWMA") (pintype "bidirectional"))
    )
    (net (code "62") (name "PWMB") (class "Default")
      (node (ref "U$1") (pin "D6") (pinfunction "D6#_D6") (pintype "bidirectional"))
      (node (ref "U$2") (pin "PWMB") (pinfunction "PWMB_PWMB") (pintype "bidirectional"))
    )
    (net (code "63") (name "SCK_BUZZ") (class "Default")
      (node (ref "AUX2") (pin "1") (pinfunction "1_1") (pintype "passive"))
      (node (ref "AUX6") (pin "1") (pinfunction "1_1") (pintype "passive"))
      (node (ref "J1") (pin "1") (pinfunction "1_1") (pintype "passive"))
      (node (ref "SPI") (pin "5") (pinfunction "5_5") (pintype "passive"))
      (node (ref "U$1") (pin "D13") (pinfunction "D13_D13") (pintype "bidirectional"))
    )
    (net (code "64") (name "SCL") (class "Default")
      (node (ref "AUX2") (pin "3") (pinfunction "3_3") (pintype "passive"))
      (node (ref "AUX6") (pin "3") (pinfunction "3_3") (pintype "passive"))
      (node (ref "DISPLAY") (pin "2") (pinfunction "2_2") (pintype "passive"))
      (node (ref "IMU") (pin "2") (pinfunction "2_2") (pintype "passive"))
      (node (ref "MCP23017_INPUTS") (pin "8") (pinfunction "8_8") (pintype "passive"))
      (node (ref "R28") (pin "1") (pinfunction "1_1") (pintype "passive"))
      (node (ref "U$1") (pin "A5") (pinfunction "A5_A5") (pintype "bidirectional"))
    )
    (net (code "65") (name "SD1") (class "Default")
      (node (ref "SD1") (pin "3") (pinfunction "3_3") (pintype "passive"))
      (node (ref "U$1") (pin "D2") (pinfunction "D2_D2") (pintype "bidirectional"))
    )
    (net (code "66") (name "SD2") (class "Default")
      (node (ref "SD2") (pin "3") (pinfunction "3_3") (pintype "passive"))
      (node (ref "U$1") (pin "A1") (pinfunction "A1_A1") (pintype "bidirectional"))
    )
    (net (code "67") (name "SD3") (class "Default")
      (node (ref "SD3") (pin "3") (pinfunction "3_3") (pintype "passive"))
      (node (ref "U$1") (pin "A0") (pinfunction "A0_A0") (pintype "bidirectional"))
    )
    (net (code "68") (name "SD4") (class "Default")
      (node (ref "SD4") (pin "3") (pinfunction "3_3") (pintype "passive"))
      (node (ref "U$1") (pin "D7") (pinfunction "D7_D7") (pintype "bidirectional"))
    )
    (net (code "69") (name "SD5") (class "Default")
      (node (ref "SD5") (pin "3") (pinfunction "3_3") (pintype "passive"))
      (node (ref "U$1") (pin "D8") (pinfunction "D8_D8") (pintype "bidirectional"))
    )
    (net (code "70") (name "SD6") (class "Default")
      (node (ref "SD6") (pin "3") (pinfunction "3_3") (pintype "passive"))
      (node (ref "U$1") (pin "D9") (pinfunction "D9#_D9") (pintype "bidirectional"))
    )
    (net (code "71") (name "SDA") (class "Default")
      (node (ref "AUX2") (pin "2") (pinfunction "2_2") (pintype "passive"))
      (node (ref "AUX6") (pin "2") (pinfunction "2_2") (pintype "passive"))
      (node (ref "DISPLAY") (pin "1") (pinfunction "1_1") (pintype "passive"))
      (node (ref "IMU") (pin "1") (pinfunction "1_1") (pintype "passive"))
      (node (ref "MCP23017_INPUTS") (pin "7") (pinfunction "7_7") (pintype "passive"))
      (node (ref "R29") (pin "1") (pinfunction "1_1") (pintype "passive"))
      (node (ref "U$1") (pin "A4") (pinfunction "A4_A4") (pintype "bidirectional"))
    )
    (net (code "72") (name "SL1") (class "Default")
      (node (ref "SL1") (pin "3") (pinfunction "3_3") (pintype "passive"))
      (node (ref "U$1") (pin "A6") (pinfunction "A6_A6") (pintype "bidirectional"))
    )
    (net (code "73") (name "SL2") (class "Default")
      (node (ref "SL2") (pin "3") (pinfunction "3_3") (pintype "passive"))
      (node (ref "U$1") (pin "A3") (pinfunction "A3_A3") (pintype "bidirectional"))
    )
    (net (code "74") (name "SL3") (class "Default")
      (node (ref "SL3") (pin "3") (pinfunction "3_3") (pintype "passive"))
      (node (ref "U$1") (pin "A2") (pinfunction "A2_A2") (pintype "bidirectional"))
    )
    (net (code "75") (name "SS") (class "Default")
      (node (ref "AUX1") (pin "3") (pinfunction "3_3") (pintype "passive"))
      (node (ref "AUX5") (pin "3") (pinfunction "3_3") (pintype "passive"))
      (node (ref "SERVO2") (pin "1") (pinfunction "1_1") (pintype "passive"))
      (node (ref "SPI") (pin "6") (pinfunction "6_6") (pintype "passive"))
      (node (ref "U$1") (pin "D10") (pinfunction "D10#_D10") (pintype "bidirectional"))
    )
    (net (code "76") (name "VCCARD") (class "Default")
      (node (ref "AUX3") (pin "3") (pinfunction "3_3") (pintype "passive"))
      (node (ref "AUX7") (pin "3") (pinfunction "3_3") (pintype "passive"))
      (node (ref "B1") (pin "2") (pinfunction "2_2") (pintype "passive"))
      (node (ref "B1B") (pin "2") (pinfunction "2_2") (pintype "passive"))
      (node (ref "BLUETOOTH1") (pin "4") (pinfunction "4_4") (pintype "passive"))
      (node (ref "DISPLAY") (pin "3") (pinfunction "3_3") (pintype "passive"))
      (node (ref "IMU") (pin "4") (pinfunction "4_4") (pintype "passive"))
      (node (ref "MCP23017_INPUTS") (pin "10") (pinfunction "10_10") (pintype "passive"))
      (node (ref "R2") (pin "2") (pinfunction "2_2") (pintype "passive"))
      (node (ref "R28") (pin "2") (pinfunction "2_2") (pintype "passive"))
      (node (ref "R29") (pin "2") (pinfunction "2_2") (pintype "passive"))
      (node (ref "S1") (pin "1") (pinfunction "1_1") (pintype "passive"))
      (node (ref "S2") (pin "1") (pinfunction "1_1") (pintype "passive"))
      (node (ref "S3") (pin "1") (pinfunction "1_1") (pintype "passive"))
      (node (ref "S4") (pin "1") (pinfunction "1_1") (pintype "passive"))
      (node (ref "SERIAL/IR") (pin "4") (pinfunction "4_4") (pintype "passive"))
      (node (ref "SPI") (pin "2") (pinfunction "2_2") (pintype "passive"))
      (node (ref "U$1") (pin "+5V") (pinfunction "+5V_+5V") (pintype "bidirectional"))
    )
    (net (code "77") (name "VCCSENS") (class "Default")
      (node (ref "7805") (pin "OUT") (pinfunction "OUT_OUT") (pintype "output"))
      (node (ref "AUX3") (pin "2") (pinfunction "2_2") (pintype "passive"))
      (node (ref "AUX7") (pin "2") (pinfunction "2_2") (pintype "passive"))
      (node (ref "C2") (pin "1") (pinfunction "1_1") (pintype "passive"))
      (node (ref "C3") (pin "+") (pinfunction "+_+") (pintype "passive"))
      (node (ref "R6") (pin "2") (pinfunction "2_2") (pintype "passive"))
      (node (ref "R7") (pin "2") (pinfunction "2_2") (pintype "passive"))
      (node (ref "SD1") (pin "1") (pinfunction "1_1") (pintype "passive"))
      (node (ref "SD2") (pin "1") (pinfunction "1_1") (pintype "passive"))
      (node (ref "SD3") (pin "1") (pinfunction "1_1") (pintype "passive"))
      (node (ref "SD4") (pin "1") (pinfunction "1_1") (pintype "passive"))
      (node (ref "SD5") (pin "1") (pinfunction "1_1") (pintype "passive"))
      (node (ref "SD6") (pin "1") (pinfunction "1_1") (pintype "passive"))
      (node (ref "SERVO1") (pin "2") (pinfunction "2_2") (pintype "passive"))
      (node (ref "SERVO2") (pin "2") (pinfunction "2_2") (pintype "passive"))
      (node (ref "SL1") (pin "2") (pinfunction "2_2") (pintype "passive"))
      (node (ref "SL2") (pin "2") (pinfunction "2_2") (pintype "passive"))
      (node (ref "SL3") (pin "2") (pinfunction "2_2") (pintype "passive"))
      (node (ref "U$2") (pin "STBY") (pinfunction "STBY_STBY") (pintype "bidirectional"))
      (node (ref "U$2") (pin "VCC") (pinfunction "VCC_VCC") (pintype "bidirectional"))
    )
    (net (code "78") (name "VINMOT") (class "Default")
      (node (ref "C4") (pin "+") (pinfunction "+_+") (pintype "passive"))
      (node (ref "GENERAL_SWITCH") (pin "B1") (pinfunction "B1_B1") (pintype "bidirectional"))
      (node (ref "U$2") (pin "VM") (pinfunction "VM_VM") (pintype "bidirectional"))
    )
    (net (code "79") (name "VINVREG") (class "Default")
      (node (ref "+BAT2") (pin "2") (pinfunction "2_2") (pintype "passive"))
      (node (ref "7805") (pin "IN") (pinfunction "IN_IN") (pintype "input"))
      (node (ref "C1") (pin "1") (pinfunction "1_1") (pintype "passive"))
      (node (ref "GENERAL_SWITCH") (pin "B2") (pinfunction "B2_B2") (pintype "bidirectional"))
      (node (ref "GENERAL_SWITCH1") (pin "B1") (pinfunction "B1_B1") (pintype "bidirectional"))
      (node (ref "GENERAL_SWITCH1") (pin "B2") (pinfunction "B2_B2") (pintype "bidirectional"))
      (node (ref "R4") (pin "1") (pinfunction "1_1") (pintype "passive"))
      (node (ref "U$1") (pin "VIN") (pinfunction "VIN_VIN") (pintype "bidirectional"))
    )
    (net (code "80") (name "VREFBAT") (class "Default")
      (node (ref "R4") (pin "2") (pinfunction "2_2") (pintype "passive"))
      (node (ref "R5") (pin "1") (pinfunction "1_1") (pintype "passive"))
      (node (ref "U$1") (pin "A7") (pinfunction "A7_A7") (pintype "bidirectional"))
    )
    (net (code "81") (name "unconnected-(U$1-Pad3V3)") (class "Default")
      (node (ref "U$1") (pin "3V3") (pinfunction "3V3_3V3") (pintype "bidirectional"))
    )
    (net (code "82") (name "unconnected-(U$1-PadAREF)") (class "Default")
      (node (ref "U$1") (pin "AREF") (pinfunction "AREF_AREF") (pintype "bidirectional"))
    )
    (net (code "83") (name "unconnected-(U$1-PadRESET)") (class "Default")
      (node (ref "U$1") (pin "RESET") (pinfunction "RESET_RESET") (pintype "bidirectional"))
    )
    (net (code "84") (name "unconnected-(U$1-PadRESET1)") (class "Default")
      (node (ref "U$1") (pin "RESET1") (pinfunction "RESET1_RESET1") (pintype "bidirectional"))
    )
  )
)
